# Main_Schematic.net
KiCad netlist of a schematic drawn in Altium Designer
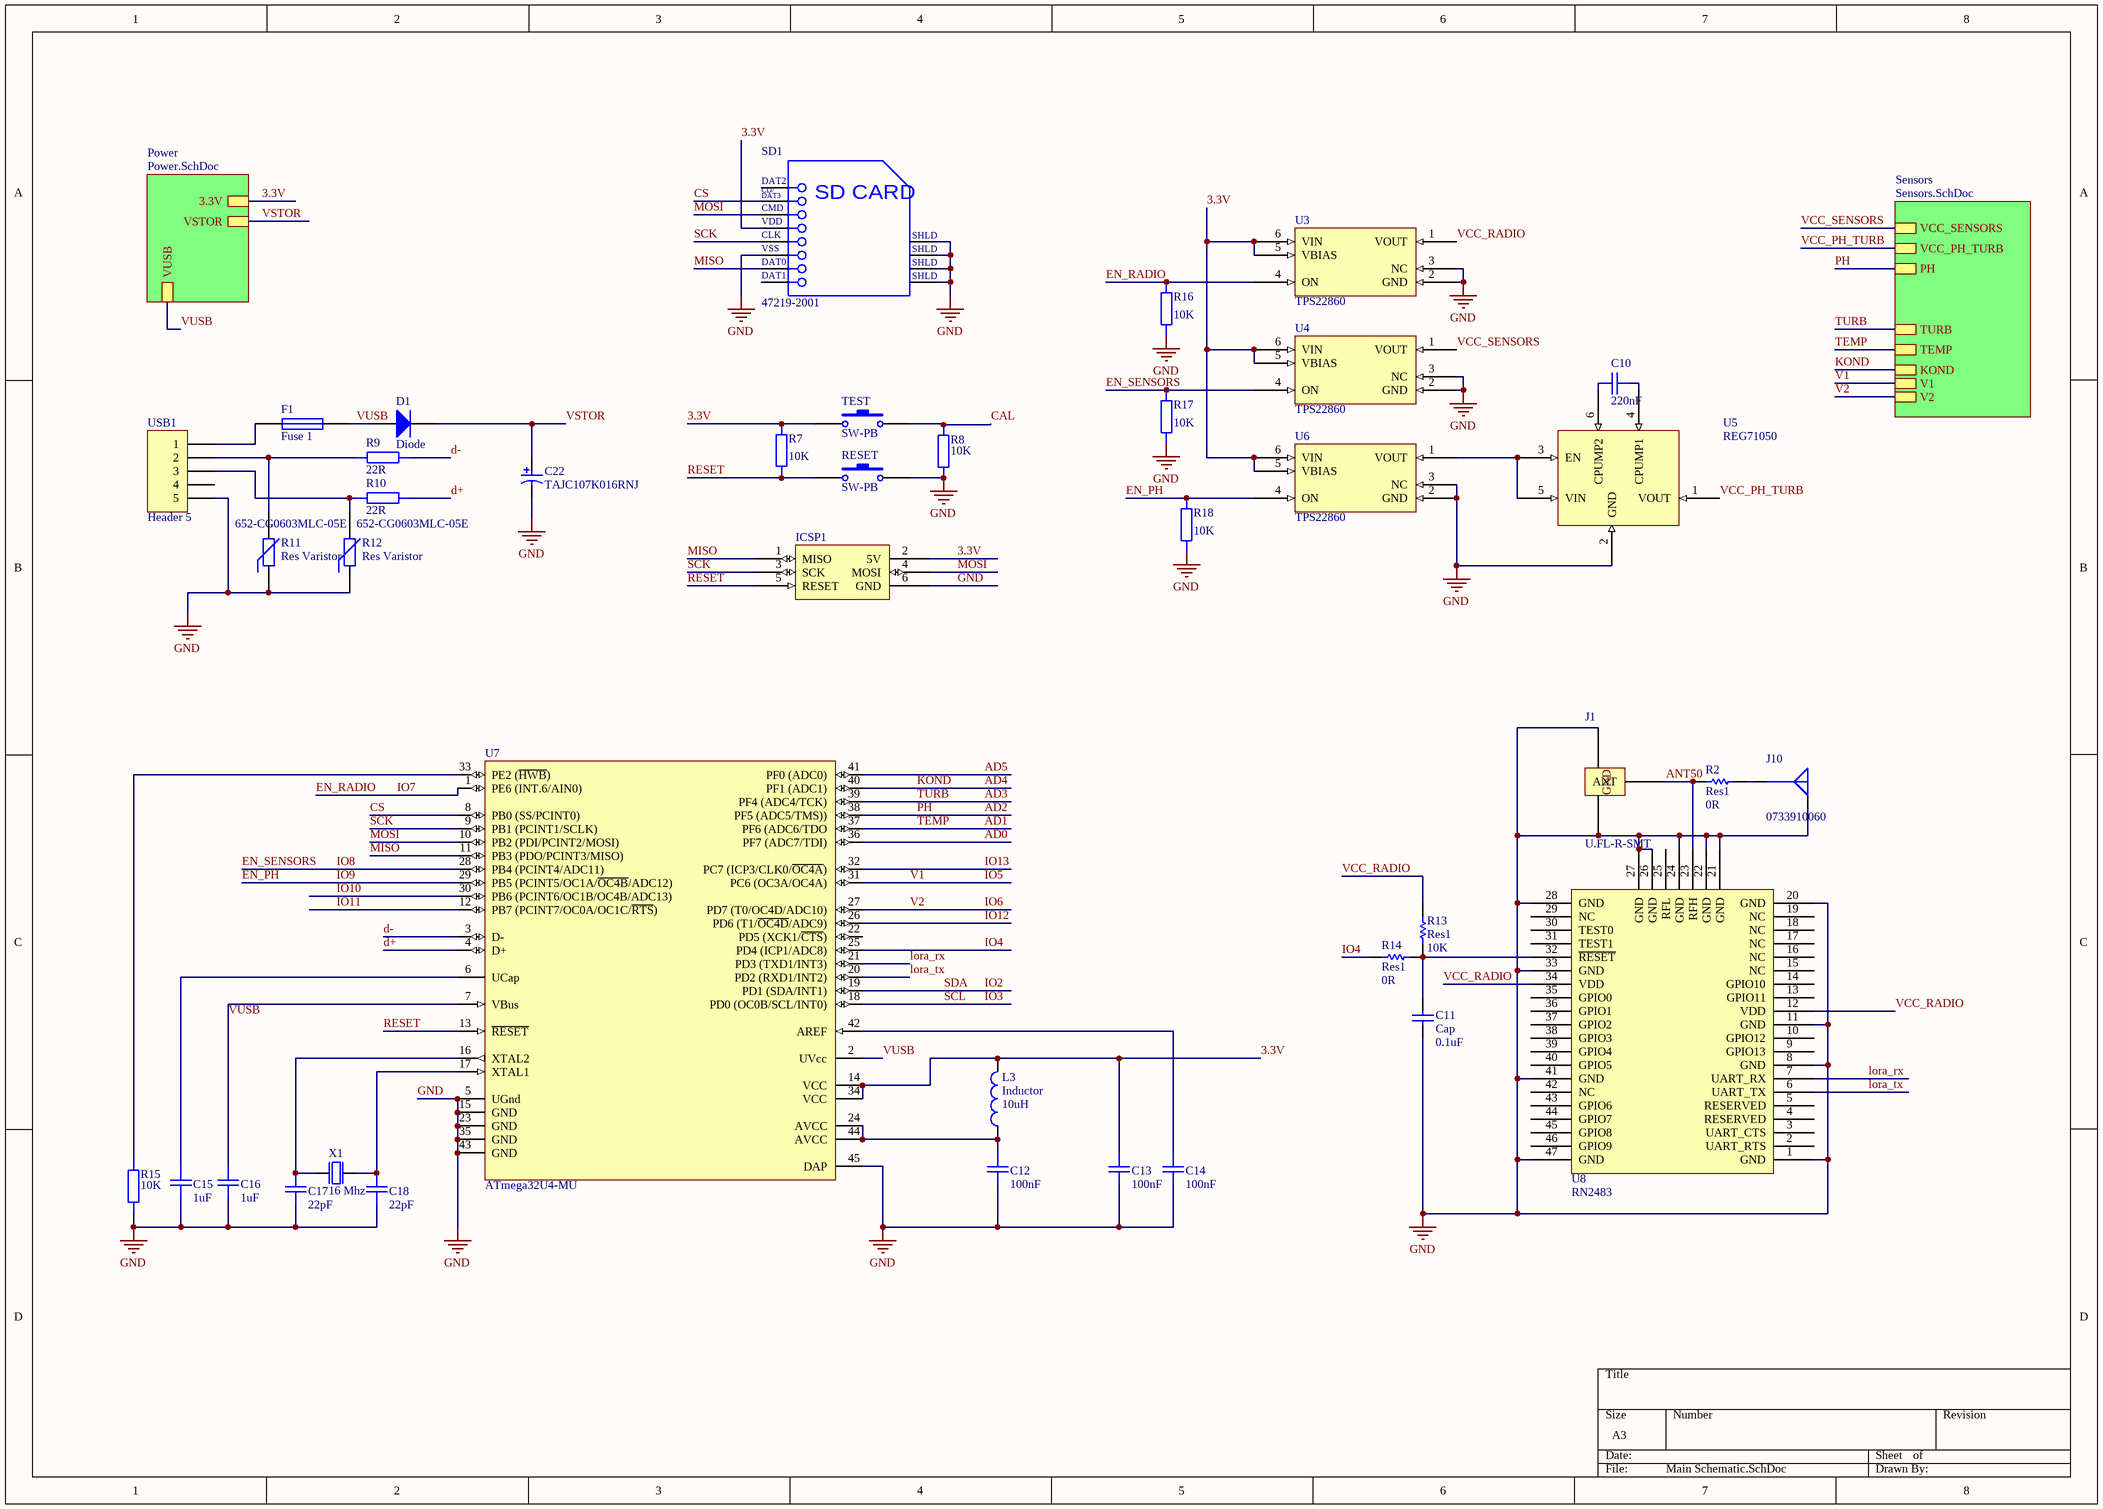
[diagram p0: Main Schematic.SchDoc]

(export (version "E")
  (design (tool "Eeschema 10.0.6"))
  (components
    (comp (ref "C10")
      (value "220nF")
      (footprint "C0805")
      (fields
        (field (name "VOLTAGE") "16V")
        (field (name "TOLERANCE") "10%")
        (field (name "Comment") "Capacitor")
      )
      (libsource (lib "Schematic Library") (part "Capacitor"))
    )
    (comp (ref "C11")
      (value "Cap")
      (footprint "C0805")
      (description "Capacitor")
      (fields (field (name "ALTIUM_VALUE") "0.1uF") (field (name "PUBLISHER") "Altium Limited"))
      (libsource (lib "Miscellaneous Devices") (part "Cap"))
    )
    (comp (ref "C12")
      (value "100nF")
      (footprint "C0805")
      (fields
        (field (name "VOLTAGE") "16V")
        (field (name "TOLERANCE") "10%")
        (field (name "Comment") "Capacitor")
      )
      (libsource (lib "Schematic Library") (part "Capacitor"))
    )
    (comp (ref "C13")
      (value "100nF")
      (footprint "C0805")
      (fields
        (field (name "VOLTAGE") "16V")
        (field (name "TOLERANCE") "10%")
        (field (name "Comment") "Capacitor")
      )
      (libsource (lib "Schematic Library") (part "Capacitor"))
    )
    (comp (ref "C14")
      (value "100nF")
      (footprint "C0805")
      (fields
        (field (name "VOLTAGE") "16V")
        (field (name "TOLERANCE") "10%")
        (field (name "Comment") "Capacitor")
      )
      (libsource (lib "Schematic Library") (part "Capacitor"))
    )
    (comp (ref "C15")
      (value "1uF")
      (footprint "C0805")
      (fields
        (field (name "VOLTAGE") "16V")
        (field (name "TOLERANCE") "10%")
        (field (name "Comment") "Capacitor")
      )
      (libsource (lib "Schematic Library") (part "Capacitor"))
    )
    (comp (ref "C16")
      (value "1uF")
      (footprint "C0805")
      (fields
        (field (name "VOLTAGE") "16V")
        (field (name "TOLERANCE") "10%")
        (field (name "Comment") "Capacitor")
      )
      (libsource (lib "Schematic Library") (part "Capacitor"))
    )
    (comp (ref "C17")
      (value "22pF")
      (footprint "C0805")
      (fields
        (field (name "VOLTAGE") "16V")
        (field (name "TOLERANCE") "10%")
        (field (name "Comment") "Capacitor")
      )
      (libsource (lib "Schematic Library") (part "Capacitor"))
    )
    (comp (ref "C18")
      (value "22pF")
      (footprint "C0805")
      (fields
        (field (name "VOLTAGE") "16V")
        (field (name "TOLERANCE") "10%")
        (field (name "Comment") "Capacitor")
      )
      (libsource (lib "Schematic Library") (part "Capacitor"))
    )
    (comp (ref "C22")
      (value "TAJC107K016RNJ")
      (footprint "AVX-TAJ-C-2_M")
      (description "Standard Tantalum, 100 uF, +/- 10%, 16 V, -55 to 125 degC, 2-Pin SMD (2312), RoHS, Tape and Reel")
      (fields (field (name "TOLERANCE") "10%") (field (name "MANUFACTURER") "AVX"))
      (libsource (lib "Altium Content Vault") (part "CAP-P-2"))
    )
    (comp (ref "D1")
      (value "Diode")
      (footprint "3216[1206]")
      (description "Default Diode")
      (fields (field (name "PUBLISHER") "Altium Limited"))
      (libsource (lib "Miscellaneous Devices") (part "Diode"))
    )
    (comp (ref "F1")
      (value "Fuse 1")
      (footprint "1812")
      (description "Fuse")
      (fields (field (name "PUBLISHER") "Altium Limited"))
      (libsource (lib "Miscellaneous Devices") (part "Fuse 1"))
    )
    (comp (ref "ICSP1") (value "ICSP") (footprint "ICSP") (libsource (lib "Header") (part "ICSP")))
    (comp (ref "J1")
      (value "U.FL-R-SMT")
      (footprint "U.FL-R-SMT")
      (libsource (lib "MnusMachina") (part "U.FL-R-SMT"))
    )
    (comp (ref "J10")
      (value "0733910060")
      (footprint "MOLEX SD-73391-0060")
      (description "CONN SMA JACK STR 50 OHM PCB")
      (libsource (lib "Celestial Library Database") (part "RF Connector - SMA"))
    )
    (comp (ref "L3")
      (value "Inductor")
      (footprint "C0603")
      (fields (field (name "ALTIUM_VALUE") "10uH") (field (name "PUBLISHER") "Altium Limited"))
      (libsource (lib "Miscellaneous Devices") (part "Inductor"))
    )
    (comp (ref "R2")
      (value "Res1")
      (footprint "6-0805_L")
      (description "Resistor")
      (fields (field (name "ALTIUM_VALUE") "0R") (field (name "PUBLISHER") "Altium Limited"))
      (libsource (lib "Miscellaneous Devices") (part "Res1"))
    )
    (comp (ref "R7")
      (value "10K")
      (footprint "6-0805_L")
      (fields (field (name "TOLERANCE") "1%") (field (name "Comment") "Resistor"))
      (libsource (lib "Schematic Library") (part "Resistor"))
    )
    (comp (ref "R8")
      (value "10K")
      (footprint "6-0805_L")
      (fields (field (name "TOLERANCE") "1%") (field (name "Comment") "Resistor"))
      (libsource (lib "Schematic Library") (part "Resistor"))
    )
    (comp (ref "R9")
      (value "22R")
      (footprint "6-0805_L")
      (fields (field (name "TOLERANCE") "1%") (field (name "Comment") "Resistor"))
      (libsource (lib "Schematic Library") (part "Resistor"))
    )
    (comp (ref "R10")
      (value "22R")
      (footprint "6-0805_L")
      (fields (field (name "TOLERANCE") "1%") (field (name "Comment") "Resistor"))
      (libsource (lib "Schematic Library") (part "Resistor"))
    )
    (comp (ref "R11")
      (value "Res Varistor")
      (footprint "6-0805_L")
      (description "Varistor (Voltage-Sensitive Resistor)")
      (fields
        (field (name "SUPPLIER PART NUMBER 1") "652-CG0603MLC-05E")
        (field (name "MANUFACTURER") "Bourns")
        (field (name "MANUFACTURER PART NUMBER") "CG0603MLC-05E")
        (field (name "PUBLISHER") "Altium Limited")
      )
      (libsource (lib "Miscellaneous Devices") (part "Res Varistor"))
    )
    (comp (ref "R12")
      (value "Res Varistor")
      (footprint "6-0805_L")
      (description "Varistor (Voltage-Sensitive Resistor)")
      (fields
        (field (name "SUPPLIER PART NUMBER 1") "652-CG0603MLC-05E")
        (field (name "MANUFACTURER") "Bourns")
        (field (name "MANUFACTURER PART NUMBER") "CG0603MLC-05E")
        (field (name "PUBLISHER") "Altium Limited")
      )
      (libsource (lib "Miscellaneous Devices") (part "Res Varistor"))
    )
    (comp (ref "R13")
      (value "Res1")
      (footprint "6-0805_L")
      (description "Resistor")
      (fields (field (name "ALTIUM_VALUE") "10K") (field (name "PUBLISHER") "Altium Limited"))
      (libsource (lib "Miscellaneous Devices") (part "Res1"))
    )
    (comp (ref "R14")
      (value "Res1")
      (footprint "6-0805_L")
      (description "Resistor")
      (fields (field (name "ALTIUM_VALUE") "0R") (field (name "PUBLISHER") "Altium Limited"))
      (libsource (lib "Miscellaneous Devices") (part "Res1"))
    )
    (comp (ref "R15")
      (value "10K")
      (footprint "6-0805_L")
      (fields (field (name "TOLERANCE") "1%") (field (name "Comment") "Resistor"))
      (libsource (lib "Schematic Library") (part "Resistor"))
    )
    (comp (ref "R16")
      (value "10K")
      (footprint "6-0805_L")
      (fields (field (name "TOLERANCE") "1%") (field (name "Comment") "Resistor"))
      (libsource (lib "Schematic Library") (part "Resistor"))
    )
    (comp (ref "R17")
      (value "10K")
      (footprint "6-0805_L")
      (fields (field (name "TOLERANCE") "1%") (field (name "Comment") "Resistor"))
      (libsource (lib "Schematic Library") (part "Resistor"))
    )
    (comp (ref "R18")
      (value "10K")
      (footprint "6-0805_L")
      (fields (field (name "TOLERANCE") "1%") (field (name "Comment") "Resistor"))
      (libsource (lib "Schematic Library") (part "Resistor"))
    )
    (comp (ref "RESET")
      (value "SW-PB")
      (footprint "BUTTON")
      (description "Switch")
      (fields (field (name "PUBLISHER") "Altium Limited"))
      (libsource (lib "Miscellaneous Devices") (part "SW-PB"))
    )
    (comp (ref "SD1")
      (value "47219-2001")
      (footprint "MOLX-47219-2001-8_V")
      (description "MicroSD Card Connector, Hinge Type, -40 to 85 degC, 8-Pin SMD, RoHS, Tape and Reel")
      (fields (field (name "MANUFACTURER") "Molex"))
      (libsource (lib "Altium Content Vault") (part "CN-SD-8-4S"))
    )
    (comp (ref "TEST")
      (value "SW-PB")
      (footprint "BUTTON")
      (description "Switch")
      (fields (field (name "PUBLISHER") "Altium Limited"))
      (libsource (lib "Miscellaneous Devices") (part "SW-PB"))
    )
    (comp (ref "U3")
      (value "TPS22860")
      (footprint "DBV PSOP")
      (description "Load switch")
      (libsource (lib "Schematic Library") (part "TPS22860"))
    )
    (comp (ref "U4")
      (value "TPS22860")
      (footprint "DBV PSOP")
      (description "Load switch")
      (libsource (lib "Schematic Library") (part "TPS22860"))
    )
    (comp (ref "U5")
      (value "REG71050")
      (footprint "DBV PSOP")
      (description "Reguator 5V")
      (libsource (lib "Schematic Library") (part "REG71050"))
    )
    (comp (ref "U6")
      (value "TPS22860")
      (footprint "DBV PSOP")
      (description "Load switch")
      (libsource (lib "Schematic Library") (part "TPS22860"))
    )
    (comp (ref "U7")
      (value "ATmega32U4-MU")
      (footprint "TQFP44")
      (fields (field (name "PUBLISHER") "Altium Limited"))
      (libsource (lib "Schematic Library") (part "ATmega32U4-MU"))
    )
    (comp (ref "U8")
      (value "RN2483")
      (footprint "RN2483 - duplicate")
      (libsource (lib "dell") (part "RN2483"))
    )
    (comp (ref "USB1")
      (value "Header 5")
      (footprint "10118193-0001LF")
      (description "Header, 5-Pin")
      (fields (field (name "PUBLISHER") "Altium Limited"))
      (libsource (lib "Miscellaneous Connectors") (part "Header 5"))
    )
    (comp (ref "X1")
      (value "16 Mhz")
      (footprint "XTAL CSM-3X")
      (description "XTAL SMD 2520, 16MHz, 8pF, ±15ppm")
      (fields
        (field (name "PART NUMBER") "NX2520SA-16MHZ-STD-CSW-5")
        (field (name "MANUFACTURER") "NDK")
        (field (name "PUBLISHER") "Nordic Semiconductor")
      )
      (libsource (lib "Nordic Discrete DB") (part "XTAL_4-pin_grounded"))
    )
  )
  (nets
    (net (code "1") (name "/3.3V") (class "Default")
      (node (ref "C13") (pin "1") (pinfunction "1_1") (pintype "passive"))
      (node (ref "ICSP1") (pin "2") (pinfunction "5V_2") (pintype "power_in"))
      (node (ref "L3") (pin "1") (pinfunction "1_1") (pintype "passive"))
      (node (ref "R7") (pin "1") (pinfunction "1_1") (pintype "passive"))
      (node (ref "SD1") (pin "4") (pinfunction "VDD_4") (pintype "passive"))
      (node (ref "TEST") (pin "1") (pinfunction "1_1") (pintype "passive"))
      (node (ref "U3") (pin "5") (pinfunction "VBIAS_5") (pintype "input"))
      (node (ref "U3") (pin "6") (pinfunction "VIN_6") (pintype "input"))
      (node (ref "U4") (pin "5") (pinfunction "VBIAS_5") (pintype "input"))
      (node (ref "U4") (pin "6") (pinfunction "VIN_6") (pintype "input"))
      (node (ref "U6") (pin "5") (pinfunction "VBIAS_5") (pintype "input"))
      (node (ref "U6") (pin "6") (pinfunction "VIN_6") (pintype "input"))
      (node (ref "U7") (pin "14") (pinfunction "VCC_14") (pintype "power_in"))
      (node (ref "U7") (pin "34") (pinfunction "VCC_34") (pintype "power_in"))
    )
    (net (code "2") (name "/AD0") (class "Default")
      (node (ref "U7") (pin "36") (pinfunction "PF7_(ADC7/TDI)_36") (pintype "bidirectional"))
    )
    (net (code "3") (name "/AD1") (class "Default")
      (node (ref "U7") (pin "37") (pinfunction "PF6_(ADC6/TDO_37") (pintype "bidirectional"))
    )
    (net (code "4") (name "/AD2") (class "Default")
      (node (ref "U7") (pin "38") (pinfunction "PF5_(ADC5/TMS))_38") (pintype "bidirectional"))
    )
    (net (code "5") (name "/AD3") (class "Default")
      (node (ref "U7") (pin "39") (pinfunction "PF4_(ADC4/TCK)_39") (pintype "bidirectional"))
    )
    (net (code "6") (name "/AD4") (class "Default")
      (node (ref "U7") (pin "40") (pinfunction "PF1_(ADC1)_40") (pintype "bidirectional"))
    )
    (net (code "7") (name "/AD5") (class "Default")
      (node (ref "U7") (pin "41") (pinfunction "PF0_(ADC0)_41") (pintype "bidirectional"))
    )
    (net (code "8") (name "/ANT50") (class "Default")
      (node (ref "J1") (pin "1") (pinfunction "ANT_1") (pintype "passive"))
      (node (ref "R2") (pin "1") (pinfunction "1_1") (pintype "passive"))
      (node (ref "U8") (pin "23") (pinfunction "RFH_23") (pintype "passive"))
    )
    (net (code "9") (name "/CAL") (class "Default")
      (node (ref "R8") (pin "1") (pinfunction "1_1") (pintype "passive"))
      (node (ref "TEST") (pin "2") (pinfunction "2_2") (pintype "passive"))
    )
    (net (code "10") (name "/CS") (class "Default")
      (node (ref "SD1") (pin "2") (pinfunction "CD/DAT3_2") (pintype "passive"))
      (node (ref "U7") (pin "8") (pinfunction "PB0_(SS/PCINT0)_8") (pintype "bidirectional"))
    )
    (net (code "11") (name "/EN_PH") (class "Default")
      (node (ref "R18") (pin "1") (pinfunction "1_1") (pintype "passive"))
      (node (ref "U6") (pin "4") (pinfunction "ON_4") (pintype "input"))
      (node (ref "U7") (pin "29") (pinfunction "PB5_(PCINT5/OC1A/~{OC4B}/ADC12)_29") (pintype "bidirectional"))
    )
    (net (code "12") (name "/EN_RADIO") (class "Default")
      (node (ref "R16") (pin "1") (pinfunction "1_1") (pintype "passive"))
      (node (ref "U3") (pin "4") (pinfunction "ON_4") (pintype "input"))
      (node (ref "U7") (pin "1") (pinfunction "PE6_(INT.6/AIN0)_1") (pintype "bidirectional"))
    )
    (net (code "13") (name "/EN_SENSORS") (class "Default")
      (node (ref "R17") (pin "1") (pinfunction "1_1") (pintype "passive"))
      (node (ref "U4") (pin "4") (pinfunction "ON_4") (pintype "input"))
      (node (ref "U7") (pin "28") (pinfunction "PB4_(PCINT4/ADC11)_28") (pintype "bidirectional"))
    )
    (net (code "14") (name "/IO2") (class "Default")
      (node (ref "U7") (pin "19") (pinfunction "PD1_(SDA/INT1)_19") (pintype "bidirectional"))
    )
    (net (code "15") (name "/IO3") (class "Default")
      (node (ref "U7") (pin "18") (pinfunction "PD0_(OC0B/SCL/INT0)_18") (pintype "bidirectional"))
    )
    (net (code "16") (name "/IO4") (class "Default")
      (node (ref "R14") (pin "1") (pinfunction "1_1") (pintype "passive"))
      (node (ref "U7") (pin "25") (pinfunction "PD4_(ICP1/ADC8)_25") (pintype "bidirectional"))
    )
    (net (code "17") (name "/IO5") (class "Default")
      (node (ref "U7") (pin "31") (pinfunction "PC6_(OC3A/OC4A)_31") (pintype "bidirectional"))
    )
    (net (code "18") (name "/IO6") (class "Default")
      (node (ref "U7") (pin "27") (pinfunction "PD7_(T0/OC4D/ADC10)_27") (pintype "bidirectional"))
    )
    (net (code "19") (name "/IO10") (class "Default")
      (node (ref "U7") (pin "30") (pinfunction "PB6_(PCINT6/OC1B/OC4B/ADC13)_30") (pintype "bidirectional"))
    )
    (net (code "20") (name "/IO11") (class "Default")
      (node (ref "U7") (pin "12") (pinfunction "PB7_(PCINT7/OC0A/OC1C/~{RTS})_12") (pintype "bidirectional"))
    )
    (net (code "21") (name "/IO12") (class "Default")
      (node (ref "U7") (pin "26") (pinfunction "PD6_(T1/~{OC4D}/ADC9)_26") (pintype "bidirectional"))
    )
    (net (code "22") (name "/IO13") (class "Default")
      (node (ref "U7") (pin "32") (pinfunction "PC7_(ICP3/CLK0/~{OC4A})_32") (pintype "bidirectional"))
    )
    (net (code "23") (name "/MISO") (class "Default")
      (node (ref "ICSP1") (pin "1") (pinfunction "MISO_1") (pintype "bidirectional"))
      (node (ref "SD1") (pin "7") (pinfunction "DAT0_7") (pintype "passive"))
      (node (ref "U7") (pin "11") (pinfunction "PB3_(PDO/PCINT3/MISO)_11") (pintype "bidirectional"))
    )
    (net (code "24") (name "/MOSI") (class "Default")
      (node (ref "ICSP1") (pin "4") (pinfunction "MOSI_4") (pintype "bidirectional"))
      (node (ref "SD1") (pin "3") (pinfunction "CMD_3") (pintype "passive"))
      (node (ref "U7") (pin "10") (pinfunction "PB2_(PDI/PCINT2/MOSI)_10") (pintype "bidirectional"))
    )
    (net (code "25") (name "/RESET") (class "Default")
      (node (ref "ICSP1") (pin "5") (pinfunction "RESET_5") (pintype "input"))
      (node (ref "R7") (pin "2") (pinfunction "2_2") (pintype "passive"))
      (node (ref "RESET") (pin "1") (pinfunction "1_1") (pintype "passive"))
      (node (ref "U7") (pin "13") (pinfunction "~{RESET}_13") (pintype "input"))
    )
    (net (code "26") (name "/SCK") (class "Default")
      (node (ref "ICSP1") (pin "3") (pinfunction "SCK_3") (pintype "bidirectional"))
      (node (ref "SD1") (pin "5") (pinfunction "CLK_5") (pintype "passive"))
      (node (ref "U7") (pin "9") (pinfunction "PB1_(PCINT1/SCLK)_9") (pintype "bidirectional"))
    )
    (net (code "27") (name "/VCC_PH_TURB") (class "Default")
      (node (ref "U5") (pin "1") (pinfunction "VOUT_1") (pintype "input"))
    )
    (net (code "28") (name "/VCC_RADIO") (class "Default")
      (node (ref "R13") (pin "1") (pinfunction "1_1") (pintype "passive"))
      (node (ref "U3") (pin "1") (pinfunction "VOUT_1") (pintype "input"))
      (node (ref "U8") (pin "12") (pinfunction "VDD_12") (pintype "passive"))
      (node (ref "U8") (pin "34") (pinfunction "VDD_34") (pintype "passive"))
    )
    (net (code "29") (name "/VCC_SENSORS") (class "Default")
      (node (ref "U4") (pin "1") (pinfunction "VOUT_1") (pintype "input"))
    )
    (net (code "30") (name "/VSTOR") (class "Default")
      (node (ref "C22") (pin "1") (pinfunction "1_1") (pintype "passive"))
      (node (ref "D1") (pin "2") (pinfunction "K_2") (pintype "passive"))
    )
    (net (code "31") (name "/VUSB") (class "Default")
      (node (ref "C16") (pin "1") (pinfunction "1_1") (pintype "passive"))
      (node (ref "D1") (pin "1") (pinfunction "A_1") (pintype "passive"))
      (node (ref "F1") (pin "2") (pinfunction "2_2") (pintype "passive"))
      (node (ref "U7") (pin "2") (pinfunction "UVcc_2") (pintype "power_in"))
      (node (ref "U7") (pin "7") (pinfunction "VBus_7") (pintype "input"))
    )
    (net (code "32") (name "/d+") (class "Default")
      (node (ref "R10") (pin "2") (pinfunction "2_2") (pintype "passive"))
      (node (ref "U7") (pin "4") (pinfunction "D+_4") (pintype "bidirectional"))
    )
    (net (code "33") (name "/d-") (class "Default")
      (node (ref "R9") (pin "2") (pinfunction "2_2") (pintype "passive"))
      (node (ref "U7") (pin "3") (pinfunction "D-_3") (pintype "bidirectional"))
    )
    (net (code "34") (name "/lora_rx") (class "Default")
      (node (ref "U7") (pin "21") (pinfunction "PD3_(TXD1/INT3)_21") (pintype "bidirectional"))
      (node (ref "U8") (pin "7") (pinfunction "UART_RX_7") (pintype "passive"))
    )
    (net (code "35") (name "/lora_tx") (class "Default")
      (node (ref "U7") (pin "20") (pinfunction "PD2_(RXD1/INT2)_20") (pintype "bidirectional"))
      (node (ref "U8") (pin "6") (pinfunction "UART_TX_6") (pintype "passive"))
    )
    (net (code "36") (name "GND") (class "Default")
      (node (ref "C11") (pin "2") (pinfunction "2_2") (pintype "passive"))
      (node (ref "C12") (pin "2") (pinfunction "2_2") (pintype "passive"))
      (node (ref "C13") (pin "2") (pinfunction "2_2") (pintype "passive"))
      (node (ref "C14") (pin "2") (pinfunction "2_2") (pintype "passive"))
      (node (ref "C15") (pin "2") (pinfunction "2_2") (pintype "passive"))
      (node (ref "C16") (pin "2") (pinfunction "2_2") (pintype "passive"))
      (node (ref "C17") (pin "2") (pinfunction "2_2") (pintype "passive"))
      (node (ref "C18") (pin "2") (pinfunction "2_2") (pintype "passive"))
      (node (ref "C22") (pin "2") (pinfunction "2_2") (pintype "passive"))
      (node (ref "ICSP1") (pin "6") (pinfunction "GND_6") (pintype "power_in"))
      (node (ref "J1") (pin "2") (pinfunction "GND_2") (pintype "power_in"))
      (node (ref "J1") (pin "3") (pinfunction "GND_3") (pintype "power_in"))
      (node (ref "J10") (pin "G") (pinfunction "G_G") (pintype "passive"))
      (node (ref "R11") (pin "1") (pinfunction "1_1") (pintype "passive"))
      (node (ref "R12") (pin "1") (pinfunction "1_1") (pintype "passive"))
      (node (ref "R15") (pin "2") (pinfunction "2_2") (pintype "passive"))
      (node (ref "R16") (pin "2") (pinfunction "2_2") (pintype "passive"))
      (node (ref "R17") (pin "2") (pinfunction "2_2") (pintype "passive"))
      (node (ref "R18") (pin "2") (pinfunction "2_2") (pintype "passive"))
      (node (ref "R8") (pin "2") (pinfunction "2_2") (pintype "passive"))
      (node (ref "RESET") (pin "2") (pinfunction "2_2") (pintype "passive"))
      (node (ref "SD1") (pin "10") (pinfunction "SHLD_10") (pintype "passive"))
      (node (ref "SD1") (pin "11") (pinfunction "SHLD_11") (pintype "passive"))
      (node (ref "SD1") (pin "12") (pinfunction "SHLD_12") (pintype "passive"))
      (node (ref "SD1") (pin "6") (pinfunction "VSS_6") (pintype "passive"))
      (node (ref "SD1") (pin "9") (pinfunction "SHLD_9") (pintype "passive"))
      (node (ref "U3") (pin "2") (pinfunction "GND_2") (pintype "input"))
      (node (ref "U3") (pin "3") (pinfunction "NC_3") (pintype "input"))
      (node (ref "U4") (pin "2") (pinfunction "GND_2") (pintype "input"))
      (node (ref "U4") (pin "3") (pinfunction "NC_3") (pintype "input"))
      (node (ref "U5") (pin "2") (pinfunction "GND_2") (pintype "input"))
      (node (ref "U6") (pin "2") (pinfunction "GND_2") (pintype "input"))
      (node (ref "U6") (pin "3") (pinfunction "NC_3") (pintype "input"))
      (node (ref "U7") (pin "15") (pinfunction "GND_15") (pintype "power_in"))
      (node (ref "U7") (pin "23") (pinfunction "GND_23") (pintype "power_in"))
      (node (ref "U7") (pin "35") (pinfunction "GND_35") (pintype "power_in"))
      (node (ref "U7") (pin "43") (pinfunction "GND_43") (pintype "power_in"))
      (node (ref "U7") (pin "45") (pinfunction "DAP_45") (pintype "power_in"))
      (node (ref "U7") (pin "5") (pinfunction "UGnd_5") (pintype "power_in"))
      (node (ref "U8") (pin "1") (pinfunction "GND_1") (pintype "passive"))
      (node (ref "U8") (pin "11") (pinfunction "GND_11") (pintype "passive"))
      (node (ref "U8") (pin "20") (pinfunction "GND_20") (pintype "passive"))
      (node (ref "U8") (pin "21") (pinfunction "GND_21") (pintype "passive"))
      (node (ref "U8") (pin "22") (pinfunction "GND_22") (pintype "passive"))
      (node (ref "U8") (pin "24") (pinfunction "GND_24") (pintype "passive"))
      (node (ref "U8") (pin "26") (pinfunction "GND_26") (pintype "passive"))
      (node (ref "U8") (pin "27") (pinfunction "GND_27") (pintype "passive"))
      (node (ref "U8") (pin "28") (pinfunction "GND_28") (pintype "passive"))
      (node (ref "U8") (pin "33") (pinfunction "GND_33") (pintype "passive"))
      (node (ref "U8") (pin "41") (pinfunction "GND_41") (pintype "passive"))
      (node (ref "U8") (pin "47") (pinfunction "GND_47") (pintype "passive"))
      (node (ref "U8") (pin "8") (pinfunction "GND_8") (pintype "passive"))
      (node (ref "USB1") (pin "5") (pinfunction "5_5") (pintype "passive"))
    )
    (net (code "37") (name "Net-(C12-Pad1)") (class "Default")
      (node (ref "C12") (pin "1") (pinfunction "1_1") (pintype "passive"))
      (node (ref "L3") (pin "2") (pinfunction "2_2") (pintype "passive"))
      (node (ref "U7") (pin "24") (pinfunction "AVCC_24") (pintype "power_in"))
      (node (ref "U7") (pin "44") (pinfunction "AVCC_44") (pintype "power_in"))
    )
    (net (code "38") (name "Net-(F1-Pad1)") (class "Default")
      (node (ref "F1") (pin "1") (pinfunction "1_1") (pintype "passive"))
      (node (ref "USB1") (pin "1") (pinfunction "1_1") (pintype "passive"))
    )
    (net (code "39") (name "Net-(J10-PadS)") (class "Default")
      (node (ref "J10") (pin "S") (pinfunction "S_S") (pintype "passive"))
      (node (ref "R2") (pin "2") (pinfunction "2_2") (pintype "passive"))
    )
    (net (code "40") (name "Net-(R10-Pad1)") (class "Default")
      (node (ref "R10") (pin "1") (pinfunction "1_1") (pintype "passive"))
      (node (ref "R12") (pin "2") (pinfunction "2_2") (pintype "passive"))
      (node (ref "USB1") (pin "3") (pinfunction "3_3") (pintype "passive"))
    )
    (net (code "41") (name "Net-(R11-Pad2)") (class "Default")
      (node (ref "R11") (pin "2") (pinfunction "2_2") (pintype "passive"))
      (node (ref "R9") (pin "1") (pinfunction "1_1") (pintype "passive"))
      (node (ref "USB1") (pin "2") (pinfunction "2_2") (pintype "passive"))
    )
    (net (code "42") (name "Net-(U5-CPUMP1)") (class "Default")
      (node (ref "C10") (pin "2") (pinfunction "2_2") (pintype "passive"))
      (node (ref "U5") (pin "4") (pinfunction "CPUMP1_4") (pintype "input"))
    )
    (net (code "43") (name "Net-(U5-CPUMP2)") (class "Default")
      (node (ref "C10") (pin "1") (pinfunction "1_1") (pintype "passive"))
      (node (ref "U5") (pin "6") (pinfunction "CPUMP2_6") (pintype "input"))
    )
    (net (code "44") (name "Net-(U5-EN)") (class "Default")
      (node (ref "U5") (pin "3") (pinfunction "EN_3") (pintype "input"))
      (node (ref "U5") (pin "5") (pinfunction "VIN_5") (pintype "input"))
      (node (ref "U6") (pin "1") (pinfunction "VOUT_1") (pintype "input"))
    )
    (net (code "45") (name "Net-(U7-AREF)") (class "Default")
      (node (ref "C14") (pin "1") (pinfunction "1_1") (pintype "passive"))
      (node (ref "U7") (pin "42") (pinfunction "AREF_42") (pintype "input"))
    )
    (net (code "46") (name "Net-(U7-PE2_(~{HWB}))") (class "Default")
      (node (ref "R15") (pin "1") (pinfunction "1_1") (pintype "passive"))
      (node (ref "U7") (pin "33") (pinfunction "PE2_(~{HWB})_33") (pintype "bidirectional"))
    )
    (net (code "47") (name "Net-(U7-UCap)") (class "Default")
      (node (ref "C15") (pin "1") (pinfunction "1_1") (pintype "passive"))
      (node (ref "U7") (pin "6") (pinfunction "UCap_6") (pintype "passive"))
    )
    (net (code "48") (name "Net-(U7-XTAL1)") (class "Default")
      (node (ref "C18") (pin "1") (pinfunction "1_1") (pintype "passive"))
      (node (ref "U7") (pin "17") (pinfunction "XTAL1_17") (pintype "input"))
      (node (ref "X1") (pin "2") (pinfunction "out_2") (pintype "passive"))
    )
    (net (code "49") (name "Net-(U7-XTAL2)") (class "Default")
      (node (ref "C17") (pin "1") (pinfunction "1_1") (pintype "passive"))
      (node (ref "U7") (pin "16") (pinfunction "XTAL2_16") (pintype "output"))
      (node (ref "X1") (pin "1") (pinfunction "inp_1") (pintype "passive"))
    )
    (net (code "50") (name "Net-(U8-~{RESET})") (class "Default")
      (node (ref "C11") (pin "1") (pinfunction "1_1") (pintype "passive"))
      (node (ref "R13") (pin "2") (pinfunction "2_2") (pintype "passive"))
      (node (ref "R14") (pin "2") (pinfunction "2_2") (pintype "passive"))
      (node (ref "U8") (pin "32") (pinfunction "~{RESET}_32") (pintype "passive"))
    )
    (net (code "51") (name "unconnected-(SD1-DAT1-Pad8)") (class "Default")
      (node (ref "SD1") (pin "8") (pinfunction "DAT1_8") (pintype "passive"))
    )
    (net (code "52") (name "unconnected-(SD1-DAT2-Pad1)") (class "Default")
      (node (ref "SD1") (pin "1") (pinfunction "DAT2_1") (pintype "passive"))
    )
    (net (code "53") (name "unconnected-(U7-PD5_(XCK1{slash}~{CTS})-Pad22)") (class "Default")
      (node (ref "U7") (pin "22") (pinfunction "PD5_(XCK1/~{CTS})_22") (pintype "bidirectional"))
    )
    (net (code "54") (name "unconnected-(U8-GPIO0-Pad35)") (class "Default")
      (node (ref "U8") (pin "35") (pinfunction "GPIO0_35") (pintype "passive"))
    )
    (net (code "55") (name "unconnected-(U8-GPIO1-Pad36)") (class "Default")
      (node (ref "U8") (pin "36") (pinfunction "GPIO1_36") (pintype "passive"))
    )
    (net (code "56") (name "unconnected-(U8-GPIO2-Pad37)") (class "Default")
      (node (ref "U8") (pin "37") (pinfunction "GPIO2_37") (pintype "passive"))
    )
    (net (code "57") (name "unconnected-(U8-GPIO3-Pad38)") (class "Default")
      (node (ref "U8") (pin "38") (pinfunction "GPIO3_38") (pintype "passive"))
    )
    (net (code "58") (name "unconnected-(U8-GPIO4-Pad39)") (class "Default")
      (node (ref "U8") (pin "39") (pinfunction "GPIO4_39") (pintype "passive"))
    )
    (net (code "59") (name "unconnected-(U8-GPIO5-Pad40)") (class "Default")
      (node (ref "U8") (pin "40") (pinfunction "GPIO5_40") (pintype "passive"))
    )
    (net (code "60") (name "unconnected-(U8-GPIO6-Pad43)") (class "Default")
      (node (ref "U8") (pin "43") (pinfunction "GPIO6_43") (pintype "passive"))
    )
    (net (code "61") (name "unconnected-(U8-GPIO7-Pad44)") (class "Default")
      (node (ref "U8") (pin "44") (pinfunction "GPIO7_44") (pintype "passive"))
    )
    (net (code "62") (name "unconnected-(U8-GPIO8-Pad45)") (class "Default")
      (node (ref "U8") (pin "45") (pinfunction "GPIO8_45") (pintype "passive"))
    )
    (net (code "63") (name "unconnected-(U8-GPIO9-Pad46)") (class "Default")
      (node (ref "U8") (pin "46") (pinfunction "GPIO9_46") (pintype "passive"))
    )
    (net (code "64") (name "unconnected-(U8-GPIO10-Pad14)") (class "Default")
      (node (ref "U8") (pin "14") (pinfunction "GPIO10_14") (pintype "passive"))
    )
    (net (code "65") (name "unconnected-(U8-GPIO11-Pad13)") (class "Default")
      (node (ref "U8") (pin "13") (pinfunction "GPIO11_13") (pintype "passive"))
    )
    (net (code "66") (name "unconnected-(U8-GPIO12-Pad10)") (class "Default")
      (node (ref "U8") (pin "10") (pinfunction "GPIO12_10") (pintype "passive"))
    )
    (net (code "67") (name "unconnected-(U8-GPIO13-Pad9)") (class "Default")
      (node (ref "U8") (pin "9") (pinfunction "GPIO13_9") (pintype "passive"))
    )
    (net (code "68") (name "unconnected-(U8-NC-Pad15)") (class "Default")
      (node (ref "U8") (pin "15") (pinfunction "NC_15") (pintype "passive"))
    )
    (net (code "69") (name "unconnected-(U8-NC-Pad16)") (class "Default")
      (node (ref "U8") (pin "16") (pinfunction "NC_16") (pintype "passive"))
    )
    (net (code "70") (name "unconnected-(U8-NC-Pad17)") (class "Default")
      (node (ref "U8") (pin "17") (pinfunction "NC_17") (pintype "passive"))
    )
    (net (code "71") (name "unconnected-(U8-NC-Pad18)") (class "Default")
      (node (ref "U8") (pin "18") (pinfunction "NC_18") (pintype "passive"))
    )
    (net (code "72") (name "unconnected-(U8-NC-Pad19)") (class "Default")
      (node (ref "U8") (pin "19") (pinfunction "NC_19") (pintype "passive"))
    )
    (net (code "73") (name "unconnected-(U8-NC-Pad29)") (class "Default")
      (node (ref "U8") (pin "29") (pinfunction "NC_29") (pintype "passive"))
    )
    (net (code "74") (name "unconnected-(U8-NC-Pad42)") (class "Default")
      (node (ref "U8") (pin "42") (pinfunction "NC_42") (pintype "passive"))
    )
    (net (code "75") (name "unconnected-(U8-RESERVED-Pad4)") (class "Default")
      (node (ref "U8") (pin "4") (pinfunction "RESERVED_4") (pintype "passive"))
    )
    (net (code "76") (name "unconnected-(U8-RESERVED-Pad5)") (class "Default")
      (node (ref "U8") (pin "5") (pinfunction "RESERVED_5") (pintype "passive"))
    )
    (net (code "77") (name "unconnected-(U8-RFL-Pad25)") (class "Default")
      (node (ref "U8") (pin "25") (pinfunction "RFL_25") (pintype "passive"))
    )
    (net (code "78") (name "unconnected-(U8-TEST0-Pad30)") (class "Default")
      (node (ref "U8") (pin "30") (pinfunction "TEST0_30") (pintype "passive"))
    )
    (net (code "79") (name "unconnected-(U8-TEST1-Pad31)") (class "Default")
      (node (ref "U8") (pin "31") (pinfunction "TEST1_31") (pintype "passive"))
    )
    (net (code "80") (name "unconnected-(U8-UART_CTS-Pad3)") (class "Default")
      (node (ref "U8") (pin "3") (pinfunction "UART_CTS_3") (pintype "passive"))
    )
    (net (code "81") (name "unconnected-(U8-UART_RTS-Pad2)") (class "Default")
      (node (ref "U8") (pin "2") (pinfunction "UART_RTS_2") (pintype "passive"))
    )
    (net (code "82") (name "unconnected-(USB1-Pad4)") (class "Default")
      (node (ref "USB1") (pin "4") (pinfunction "4_4") (pintype "passive"))
    )
  )
)
